# watch_game_2022_revB.net
KiCad netlist of a schematic drawn in EAGLE
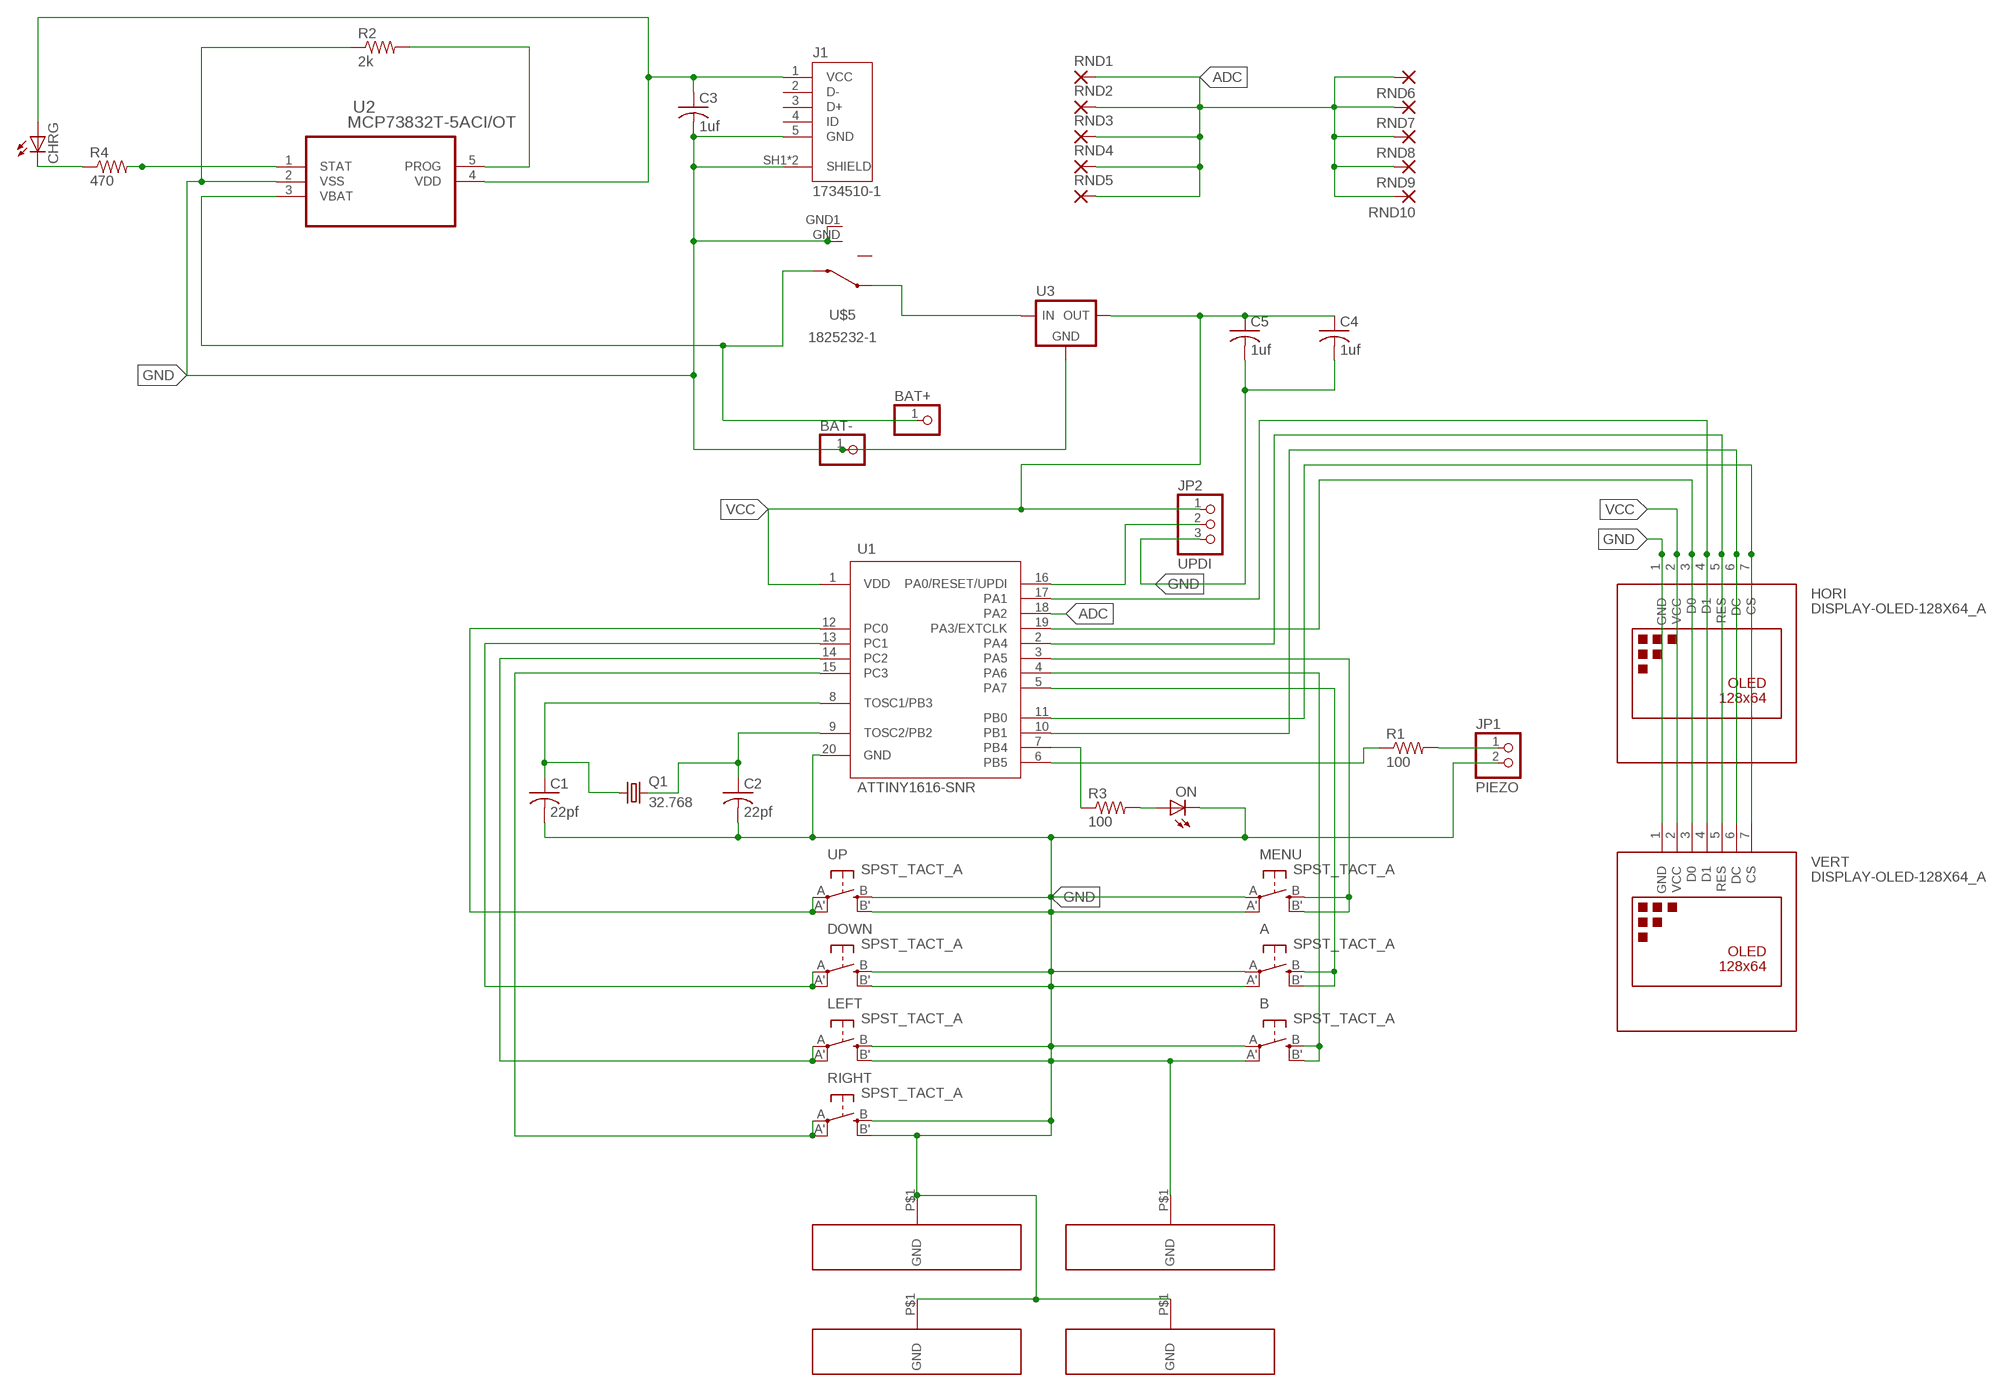
[diagram p0: schematic, sheet 1]

(export (version "E")
  (design (tool "Eeschema 10.0.6"))
  (components
    (comp (ref "A")
      (value "SPST_TACT_A")
      (footprint "eagle-import:EVQ-Q2_A")
      (libsource (lib "eagle-import") (part "SPST_TACT_A"))
    )
    (comp (ref "B")
      (value "SPST_TACT_A")
      (footprint "eagle-import:EVQ-Q2_A")
      (libsource (lib "eagle-import") (part "SPST_TACT_A"))
    )
    (comp (ref "BAT+")
      (value "PINHD-1X1")
      (footprint "eagle-import:1X01")
      (libsource (lib "eagle-import") (part "PINHD-1X1"))
    )
    (comp (ref "BAT-")
      (value "PINHD-1X1")
      (footprint "eagle-import:1X01")
      (libsource (lib "eagle-import") (part "PINHD-1X1"))
    )
    (comp (ref "C1")
      (value "22pf")
      (footprint "eagle-import:C0805")
      (libsource (lib "eagle-import") (part "C-USC0805"))
    )
    (comp (ref "C2")
      (value "22pf")
      (footprint "eagle-import:C0805")
      (libsource (lib "eagle-import") (part "C-USC0805"))
    )
    (comp (ref "C3")
      (value "1uf")
      (footprint "eagle-import:C0805")
      (libsource (lib "eagle-import") (part "rcl_334_C-USC0805"))
    )
    (comp (ref "C4")
      (value "1uf")
      (footprint "eagle-import:C0805")
      (libsource (lib "eagle-import") (part "rcl_334_C-USC0805"))
    )
    (comp (ref "C5")
      (value "1uf")
      (footprint "eagle-import:C0805")
      (libsource (lib "eagle-import") (part "rcl_334_C-USC0805"))
    )
    (comp (ref "CHRG")
      (value "LED3MM")
      (footprint "eagle-import:LED3MM")
      (libsource (lib "eagle-import") (part "LED3MM"))
    )
    (comp (ref "DOWN")
      (value "SPST_TACT_A")
      (footprint "eagle-import:EVQ-Q2_A")
      (libsource (lib "eagle-import") (part "SPST_TACT_A"))
    )
    (comp (ref "HORI")
      (value "DISPLAY-OLED-128X64_A")
      (footprint "eagle-import:DISPLAY-OLED-128X64_A")
      (libsource (lib "eagle-import") (part "DISPLAY-OLED-128X64_A"))
    )
    (comp (ref "J1")
      (value "1734510-1")
      (footprint "eagle-import:TE_1734510-1")
      (fields (field (name "MF") "TE Connectivity"))
      (libsource (lib "eagle-import") (part "1734510-1"))
    )
    (comp (ref "JP1")
      (value "PIEZO")
      (footprint "eagle-import:1X02")
      (libsource (lib "eagle-import") (part "PINHD-1X2"))
    )
    (comp (ref "JP2")
      (value "UPDI")
      (footprint "eagle-import:1X03")
      (libsource (lib "eagle-import") (part "PINHD-1X3"))
    )
    (comp (ref "LEFT")
      (value "SPST_TACT_A")
      (footprint "eagle-import:EVQ-Q2_A")
      (libsource (lib "eagle-import") (part "SPST_TACT_A"))
    )
    (comp (ref "MENU")
      (value "SPST_TACT_A")
      (footprint "eagle-import:EVQ-Q2_A")
      (libsource (lib "eagle-import") (part "SPST_TACT_A"))
    )
    (comp (ref "ON")
      (value "LED5MM")
      (footprint "eagle-import:LED5MM")
      (libsource (lib "eagle-import") (part "led_259_LED5MM"))
    )
    (comp (ref "Q1")
      (value "32.768")
      (footprint "eagle-import:TC26H")
      (libsource (lib "eagle-import") (part "CRYSTALTC26H"))
    )
    (comp (ref "R1")
      (value "100")
      (footprint "eagle-import:M0805")
      (libsource (lib "eagle-import") (part "R-US_M0805"))
    )
    (comp (ref "R2")
      (value "2k")
      (footprint "eagle-import:M0805")
      (libsource (lib "eagle-import") (part "R-US_M0805"))
    )
    (comp (ref "R3")
      (value "100")
      (footprint "eagle-import:M0805")
      (libsource (lib "eagle-import") (part "R-US_M0805"))
    )
    (comp (ref "R4")
      (value "470")
      (footprint "eagle-import:M0805")
      (libsource (lib "eagle-import") (part "R-US_M0805"))
    )
    (comp (ref "RIGHT")
      (value "SPST_TACT_A")
      (footprint "eagle-import:EVQ-Q2_A")
      (libsource (lib "eagle-import") (part "SPST_TACT_A"))
    )
    (comp (ref "RND1")
      (value "SMD5")
      (footprint "eagle-import:SMD2,54-5,08")
      (libsource (lib "eagle-import") (part "SMD5"))
    )
    (comp (ref "RND2")
      (value "SMD5")
      (footprint "eagle-import:SMD2,54-5,08")
      (libsource (lib "eagle-import") (part "SMD5"))
    )
    (comp (ref "RND3")
      (value "SMD5")
      (footprint "eagle-import:SMD2,54-5,08")
      (libsource (lib "eagle-import") (part "SMD5"))
    )
    (comp (ref "RND4")
      (value "SMD5")
      (footprint "eagle-import:SMD2,54-5,08")
      (libsource (lib "eagle-import") (part "SMD5"))
    )
    (comp (ref "RND5")
      (value "SMD5")
      (footprint "eagle-import:SMD2,54-5,08")
      (libsource (lib "eagle-import") (part "SMD5"))
    )
    (comp (ref "RND6")
      (value "SMD5")
      (footprint "eagle-import:SMD2,54-5,08")
      (libsource (lib "eagle-import") (part "SMD5"))
    )
    (comp (ref "RND7")
      (value "SMD5")
      (footprint "eagle-import:SMD2,54-5,08")
      (libsource (lib "eagle-import") (part "SMD5"))
    )
    (comp (ref "RND8")
      (value "SMD5")
      (footprint "eagle-import:SMD2,54-5,08")
      (libsource (lib "eagle-import") (part "SMD5"))
    )
    (comp (ref "RND9")
      (value "SMD5")
      (footprint "eagle-import:SMD2,54-5,08")
      (libsource (lib "eagle-import") (part "SMD5"))
    )
    (comp (ref "RND10")
      (value "SMD5")
      (footprint "eagle-import:SMD2,54-5,08")
      (libsource (lib "eagle-import") (part "SMD5"))
    )
    (comp (ref "U$5")
      (value "1825232-1")
      (footprint "eagle-import:1825232-1")
      (fields (field (name "MF") "TE Connectivity"))
      (libsource (lib "eagle-import") (part "1825232-1"))
    )
    (comp (ref "U$6")
      (value "GND_STRIP_600MIL")
      (footprint "eagle-import:GND_PADS_2")
      (libsource (lib "eagle-import") (part "GND_STRIP_600MIL"))
    )
    (comp (ref "U$7")
      (value "GND_STRIP_600MIL")
      (footprint "eagle-import:GND_PADS_2")
      (libsource (lib "eagle-import") (part "GND_STRIP_600MIL"))
    )
    (comp (ref "U$8")
      (value "GND_STRIP_600MIL")
      (footprint "eagle-import:GND_PADS_2")
      (libsource (lib "eagle-import") (part "GND_STRIP_600MIL"))
    )
    (comp (ref "U$9")
      (value "GND_STRIP_600MIL")
      (footprint "eagle-import:GND_PADS_2")
      (libsource (lib "eagle-import") (part "GND_STRIP_600MIL"))
    )
    (comp (ref "U1")
      (value "ATTINY1616-SNR")
      (footprint "eagle-import:SOIC127P1032X265-20N")
      (fields (field (name "MF") "Microchip"))
      (libsource (lib "eagle-import") (part "ATTINY1616-SNR"))
    )
    (comp (ref "U2")
      (value "MCP73832T-5ACI/OT")
      (footprint "eagle-import:SOT95P300X145-5N")
      (fields (field (name "MF") "Microchip"))
      (libsource (lib "eagle-import") (part "MCP73832T-5ACI/OT"))
    )
    (comp (ref "U3")
      (value "LF50CDT")
      (footprint "eagle-import:DPAK")
      (libsource (lib "eagle-import") (part "LF50CDT"))
    )
    (comp (ref "UP")
      (value "SPST_TACT_A")
      (footprint "eagle-import:EVQ-Q2_A")
      (libsource (lib "eagle-import") (part "SPST_TACT_A"))
    )
    (comp (ref "VERT")
      (value "DISPLAY-OLED-128X64_A")
      (footprint "eagle-import:DISPLAY-OLED-128X64_A")
      (libsource (lib "eagle-import") (part "DISPLAY-OLED-128X64_A"))
    )
  )
  (nets
    (net (code "1") (name "ADC") (class "Default")
      (node (ref "RND1") (pin "1") (pinfunction "P_1") (pintype "passive"))
      (node (ref "RND10") (pin "1") (pinfunction "P_1") (pintype "passive"))
      (node (ref "RND2") (pin "1") (pinfunction "P_1") (pintype "passive"))
      (node (ref "RND3") (pin "1") (pinfunction "P_1") (pintype "passive"))
      (node (ref "RND4") (pin "1") (pinfunction "P_1") (pintype "passive"))
      (node (ref "RND5") (pin "1") (pinfunction "P_1") (pintype "passive"))
      (node (ref "RND6") (pin "1") (pinfunction "P_1") (pintype "passive"))
      (node (ref "RND7") (pin "1") (pinfunction "P_1") (pintype "passive"))
      (node (ref "RND8") (pin "1") (pinfunction "P_1") (pintype "passive"))
      (node (ref "RND9") (pin "1") (pinfunction "P_1") (pintype "passive"))
      (node (ref "U1") (pin "18") (pinfunction "PA2_18") (pintype "bidirectional"))
    )
    (net (code "2") (name "GND") (class "Default")
      (node (ref "A") (pin "A") (pinfunction "P_A") (pintype "passive"))
      (node (ref "A") (pin "A'") (pinfunction "P1_A'") (pintype "passive"))
      (node (ref "B") (pin "A") (pinfunction "P_A") (pintype "passive"))
      (node (ref "B") (pin "A'") (pinfunction "P1_A'") (pintype "passive"))
      (node (ref "BAT-") (pin "1") (pinfunction "1_1") (pintype "passive"))
      (node (ref "C1") (pin "2") (pinfunction "2_2") (pintype "passive"))
      (node (ref "C2") (pin "2") (pinfunction "2_2") (pintype "passive"))
      (node (ref "C3") (pin "2") (pinfunction "2_2") (pintype "passive"))
      (node (ref "C4") (pin "2") (pinfunction "2_2") (pintype "passive"))
      (node (ref "C5") (pin "2") (pinfunction "2_2") (pintype "passive"))
      (node (ref "DOWN") (pin "B") (pinfunction "S_B") (pintype "passive"))
      (node (ref "DOWN") (pin "B'") (pinfunction "S1_B'") (pintype "passive"))
      (node (ref "HORI") (pin "1") (pinfunction "GND_1") (pintype "power_in"))
      (node (ref "J1") (pin "5") (pinfunction "GND_5") (pintype "passive"))
      (node (ref "J1") (pin "SH1") (pinfunction "SHIELD_SH1") (pintype "passive"))
      (node (ref "J1") (pin "SH2") (pinfunction "SHIELD_SH2") (pintype "passive"))
      (node (ref "JP1") (pin "2") (pinfunction "2_2") (pintype "passive"))
      (node (ref "JP2") (pin "3") (pinfunction "3_3") (pintype "passive"))
      (node (ref "LEFT") (pin "B") (pinfunction "S_B") (pintype "passive"))
      (node (ref "LEFT") (pin "B'") (pinfunction "S1_B'") (pintype "passive"))
      (node (ref "MENU") (pin "A") (pinfunction "P_A") (pintype "passive"))
      (node (ref "MENU") (pin "A'") (pinfunction "P1_A'") (pintype "passive"))
      (node (ref "ON") (pin "K") (pinfunction "C_K") (pintype "passive"))
      (node (ref "R2") (pin "1") (pinfunction "1_1") (pintype "passive"))
      (node (ref "RIGHT") (pin "B") (pinfunction "S_B") (pintype "passive"))
      (node (ref "RIGHT") (pin "B'") (pinfunction "S1_B'") (pintype "passive"))
      (node (ref "U$5") (pin "GND") (pinfunction "GND_GND") (pintype "passive"))
      (node (ref "U$5") (pin "GND1") (pinfunction "GND1_GND1") (pintype "passive"))
      (node (ref "U$6") (pin "P$1") (pinfunction "GND_P$1") (pintype "bidirectional"))
      (node (ref "U$7") (pin "P$1") (pinfunction "GND_P$1") (pintype "bidirectional"))
      (node (ref "U$8") (pin "P$1") (pinfunction "GND_P$1") (pintype "bidirectional"))
      (node (ref "U$9") (pin "P$1") (pinfunction "GND_P$1") (pintype "bidirectional"))
      (node (ref "U1") (pin "20") (pinfunction "GND_20") (pintype "power_in"))
      (node (ref "U2") (pin "2") (pinfunction "VSS_2") (pintype "passive"))
      (node (ref "U3") (pin "4") (pinfunction "GND_4") (pintype "power_in"))
      (node (ref "UP") (pin "B") (pinfunction "S_B") (pintype "passive"))
      (node (ref "UP") (pin "B'") (pinfunction "S1_B'") (pintype "passive"))
      (node (ref "VERT") (pin "1") (pinfunction "GND_1") (pintype "power_in"))
    )
    (net (code "3") (name "Net-(A-S)") (class "Default")
      (node (ref "A") (pin "B") (pinfunction "S_B") (pintype "passive"))
      (node (ref "A") (pin "B'") (pinfunction "S1_B'") (pintype "passive"))
      (node (ref "U1") (pin "5") (pinfunction "PA7_5") (pintype "bidirectional"))
    )
    (net (code "4") (name "Net-(B-S)") (class "Default")
      (node (ref "B") (pin "B") (pinfunction "S_B") (pintype "passive"))
      (node (ref "B") (pin "B'") (pinfunction "S1_B'") (pintype "passive"))
      (node (ref "U1") (pin "4") (pinfunction "PA6_4") (pintype "bidirectional"))
    )
    (net (code "5") (name "Net-(CHRG-C)") (class "Default")
      (node (ref "CHRG") (pin "K") (pinfunction "C_K") (pintype "passive"))
      (node (ref "R4") (pin "1") (pinfunction "1_1") (pintype "passive"))
    )
    (net (code "6") (name "Net-(DOWN-P)") (class "Default")
      (node (ref "DOWN") (pin "A") (pinfunction "P_A") (pintype "passive"))
      (node (ref "DOWN") (pin "A'") (pinfunction "P1_A'") (pintype "passive"))
      (node (ref "U1") (pin "13") (pinfunction "PC1_13") (pintype "bidirectional"))
    )
    (net (code "7") (name "Net-(HORI-CS)") (class "Default")
      (node (ref "HORI") (pin "7") (pinfunction "CS_7") (pintype "bidirectional"))
      (node (ref "U1") (pin "11") (pinfunction "PB0_11") (pintype "bidirectional"))
      (node (ref "VERT") (pin "7") (pinfunction "CS_7") (pintype "bidirectional"))
    )
    (net (code "8") (name "Net-(HORI-D0)") (class "Default")
      (node (ref "HORI") (pin "3") (pinfunction "D0_3") (pintype "bidirectional"))
      (node (ref "U1") (pin "19") (pinfunction "PA3/EXTCLK_19") (pintype "bidirectional"))
      (node (ref "VERT") (pin "3") (pinfunction "D0_3") (pintype "bidirectional"))
    )
    (net (code "9") (name "Net-(HORI-D1)") (class "Default")
      (node (ref "HORI") (pin "4") (pinfunction "D1_4") (pintype "bidirectional"))
      (node (ref "U1") (pin "17") (pinfunction "PA1_17") (pintype "bidirectional"))
      (node (ref "VERT") (pin "4") (pinfunction "D1_4") (pintype "bidirectional"))
    )
    (net (code "10") (name "Net-(HORI-DC)") (class "Default")
      (node (ref "HORI") (pin "6") (pinfunction "DC_6") (pintype "bidirectional"))
      (node (ref "U1") (pin "10") (pinfunction "PB1_10") (pintype "bidirectional"))
      (node (ref "VERT") (pin "6") (pinfunction "DC_6") (pintype "bidirectional"))
    )
    (net (code "11") (name "Net-(HORI-RES)") (class "Default")
      (node (ref "HORI") (pin "5") (pinfunction "RES_5") (pintype "bidirectional"))
      (node (ref "U1") (pin "2") (pinfunction "PA4_2") (pintype "bidirectional"))
      (node (ref "VERT") (pin "5") (pinfunction "RES_5") (pintype "bidirectional"))
    )
    (net (code "12") (name "Net-(J1-VCC)") (class "Default")
      (node (ref "C3") (pin "1") (pinfunction "1_1") (pintype "passive"))
      (node (ref "CHRG") (pin "A") (pinfunction "A_A") (pintype "passive"))
      (node (ref "J1") (pin "1") (pinfunction "VCC_1") (pintype "passive"))
      (node (ref "U2") (pin "4") (pinfunction "VDD_4") (pintype "power_in"))
    )
    (net (code "13") (name "Net-(JP1-Pad1)") (class "Default")
      (node (ref "JP1") (pin "1") (pinfunction "1_1") (pintype "passive"))
      (node (ref "R1") (pin "2") (pinfunction "2_2") (pintype "passive"))
    )
    (net (code "14") (name "Net-(LEFT-P)") (class "Default")
      (node (ref "LEFT") (pin "A") (pinfunction "P_A") (pintype "passive"))
      (node (ref "LEFT") (pin "A'") (pinfunction "P1_A'") (pintype "passive"))
      (node (ref "U1") (pin "14") (pinfunction "PC2_14") (pintype "bidirectional"))
    )
    (net (code "15") (name "Net-(MENU-S)") (class "Default")
      (node (ref "MENU") (pin "B") (pinfunction "S_B") (pintype "passive"))
      (node (ref "MENU") (pin "B'") (pinfunction "S1_B'") (pintype "passive"))
      (node (ref "U1") (pin "3") (pinfunction "PA5_3") (pintype "bidirectional"))
    )
    (net (code "16") (name "Net-(ON-PadA)") (class "Default")
      (node (ref "ON") (pin "A") (pinfunction "A_A") (pintype "passive"))
      (node (ref "R3") (pin "2") (pinfunction "2_2") (pintype "passive"))
    )
    (net (code "17") (name "Net-(RIGHT-P)") (class "Default")
      (node (ref "RIGHT") (pin "A") (pinfunction "P_A") (pintype "passive"))
      (node (ref "RIGHT") (pin "A'") (pinfunction "P1_A'") (pintype "passive"))
      (node (ref "U1") (pin "15") (pinfunction "PC3_15") (pintype "bidirectional"))
    )
    (net (code "18") (name "Net-(U1-PA0{slash}RESET{slash}UPDI)") (class "Default")
      (node (ref "JP2") (pin "2") (pinfunction "2_2") (pintype "passive"))
      (node (ref "U1") (pin "16") (pinfunction "PA0/RESET/UPDI_16") (pintype "bidirectional"))
    )
    (net (code "19") (name "Net-(U1-PB4)") (class "Default")
      (node (ref "R3") (pin "1") (pinfunction "1_1") (pintype "passive"))
      (node (ref "U1") (pin "7") (pinfunction "PB4_7") (pintype "bidirectional"))
    )
    (net (code "20") (name "Net-(U1-PB5)") (class "Default")
      (node (ref "R1") (pin "1") (pinfunction "1_1") (pintype "passive"))
      (node (ref "U1") (pin "6") (pinfunction "PB5_6") (pintype "bidirectional"))
    )
    (net (code "21") (name "Net-(U1-PC0)") (class "Default")
      (node (ref "U1") (pin "12") (pinfunction "PC0_12") (pintype "bidirectional"))
      (node (ref "UP") (pin "A") (pinfunction "P_A") (pintype "passive"))
      (node (ref "UP") (pin "A'") (pinfunction "P1_A'") (pintype "passive"))
    )
    (net (code "22") (name "Net-(U1-TOSC1{slash}PB3)") (class "Default")
      (node (ref "C1") (pin "1") (pinfunction "1_1") (pintype "passive"))
      (node (ref "Q1") (pin "1") (pinfunction "1_1") (pintype "passive"))
      (node (ref "U1") (pin "8") (pinfunction "TOSC1/PB3_8") (pintype "bidirectional"))
    )
    (net (code "23") (name "Net-(U1-TOSC2{slash}PB2)") (class "Default")
      (node (ref "C2") (pin "1") (pinfunction "1_1") (pintype "passive"))
      (node (ref "Q1") (pin "2") (pinfunction "2_2") (pintype "passive"))
      (node (ref "U1") (pin "9") (pinfunction "TOSC2/PB2_9") (pintype "bidirectional"))
    )
    (net (code "24") (name "Net-(U2-PROG)") (class "Default")
      (node (ref "R2") (pin "2") (pinfunction "2_2") (pintype "passive"))
      (node (ref "U2") (pin "5") (pinfunction "PROG_5") (pintype "input"))
    )
    (net (code "25") (name "Net-(U2-STAT)") (class "Default")
      (node (ref "R4") (pin "2") (pinfunction "2_2") (pintype "passive"))
      (node (ref "U2") (pin "1") (pinfunction "STAT_1") (pintype "input"))
    )
    (net (code "26") (name "Net-(U2-VBAT)") (class "Default")
      (node (ref "BAT+") (pin "1") (pinfunction "1_1") (pintype "passive"))
      (node (ref "U$5") (pin "2") (pinfunction "2_2") (pintype "passive"))
      (node (ref "U2") (pin "3") (pinfunction "VBAT_3") (pintype "input"))
    )
    (net (code "27") (name "Net-(U3-VIN)") (class "Default")
      (node (ref "U$5") (pin "3") (pinfunction "3_3") (pintype "passive"))
      (node (ref "U3") (pin "1") (pinfunction "VIN_1") (pintype "power_in"))
    )
    (net (code "28") (name "VCC") (class "Default")
      (node (ref "C4") (pin "1") (pinfunction "1_1") (pintype "passive"))
      (node (ref "C5") (pin "1") (pinfunction "1_1") (pintype "passive"))
      (node (ref "HORI") (pin "2") (pinfunction "VCC_2") (pintype "power_in"))
      (node (ref "JP2") (pin "1") (pinfunction "1_1") (pintype "passive"))
      (node (ref "U1") (pin "1") (pinfunction "VDD_1") (pintype "power_in"))
      (node (ref "U3") (pin "3") (pinfunction "VOUT_3") (pintype "power_in"))
      (node (ref "VERT") (pin "2") (pinfunction "VCC_2") (pintype "power_in"))
    )
    (net (code "29") (name "unconnected-(J1-D+-Pad3)") (class "Default")
      (node (ref "J1") (pin "3") (pinfunction "D+_3") (pintype "passive"))
    )
    (net (code "30") (name "unconnected-(J1-D--Pad2)") (class "Default")
      (node (ref "J1") (pin "2") (pinfunction "D-_2") (pintype "passive"))
    )
    (net (code "31") (name "unconnected-(J1-ID-Pad4)") (class "Default")
      (node (ref "J1") (pin "4") (pinfunction "ID_4") (pintype "passive"))
    )
    (net (code "32") (name "unconnected-(U$5-Pad1)") (class "Default")
      (node (ref "U$5") (pin "1") (pinfunction "1_1") (pintype "passive"))
    )
  )
)
